# mm5833.net
KiCad netlist of a schematic drawn in EAGLE
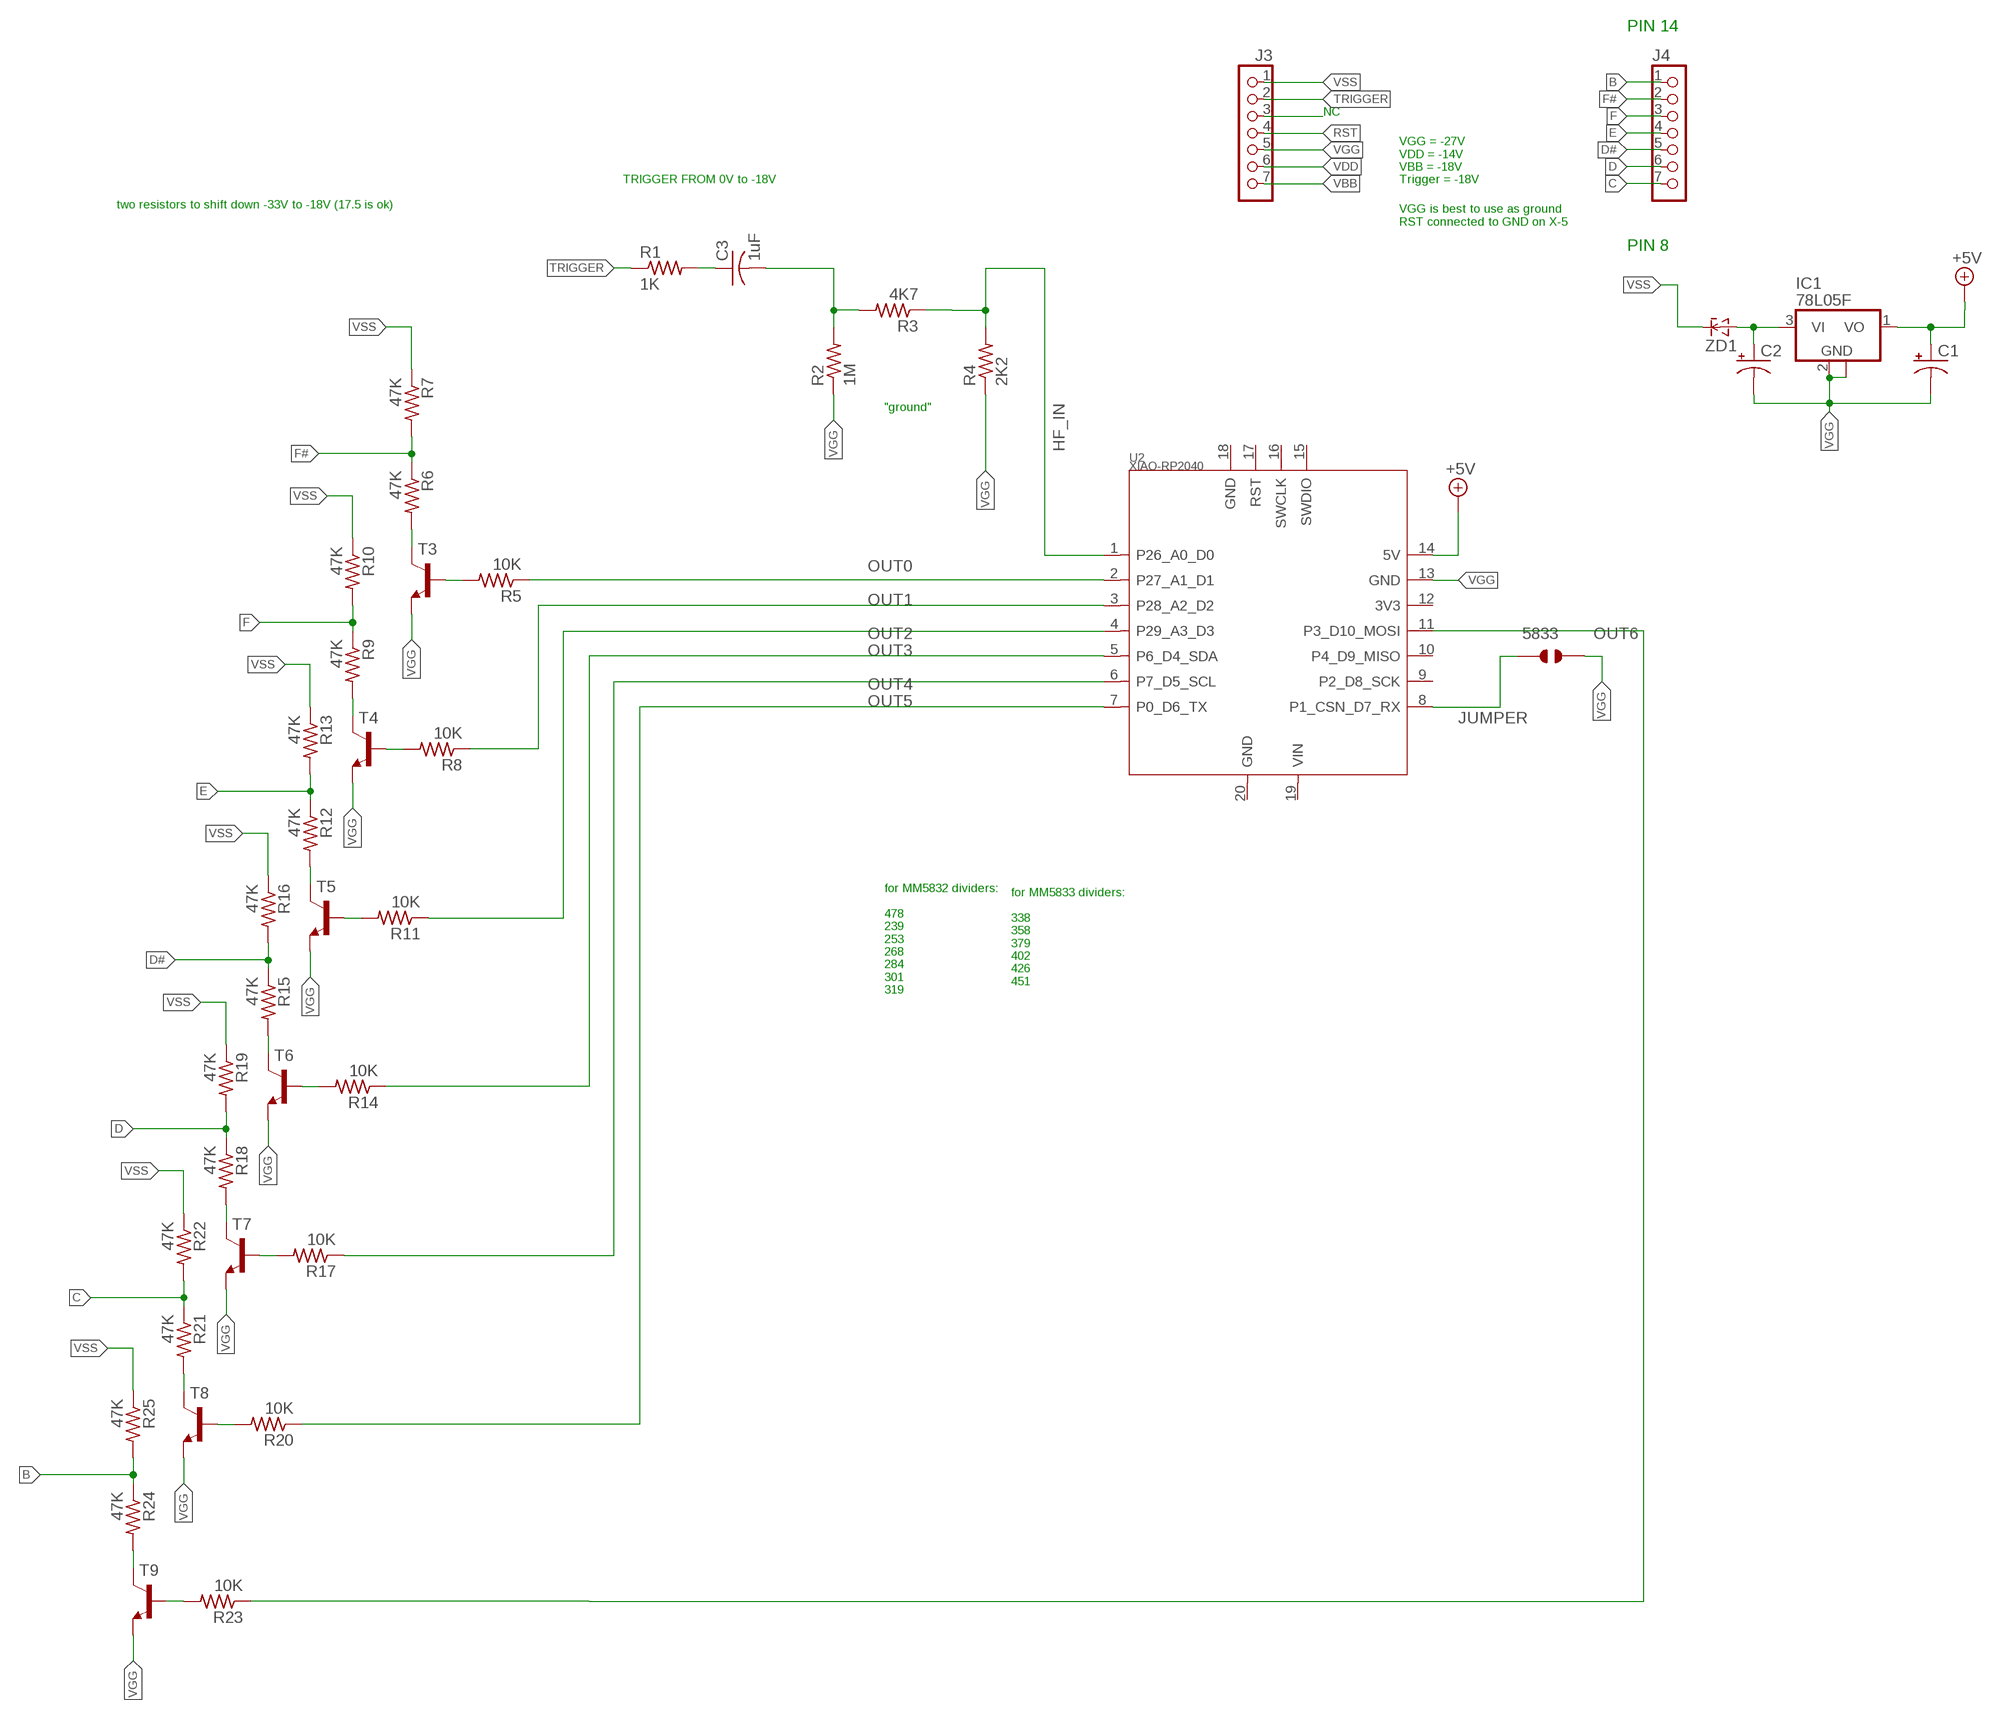
[diagram p0: schematic, sheet 1]

(export (version "E")
  (design (tool "Eeschema 10.0.6"))
  (components
    (comp (ref "5833")
      (value "JUMPER_SOLDER_1X2")
      (footprint "eagle-import:JUMPER_SOLDER_1X2")
      (libsource (lib "eagle-import") (part "JUMPER_SOLDER_1X2"))
    )
    (comp (ref "C1")
      (value "CPOL-USA/3216-18R")
      (footprint "eagle-import:A_3216-18R")
      (libsource (lib "eagle-import") (part "CPOL-USA/3216-18R"))
    )
    (comp (ref "C2")
      (value "CPOL-USA/3216-18R")
      (footprint "eagle-import:A_3216-18R")
      (libsource (lib "eagle-import") (part "CPOL-USA/3216-18R"))
    )
    (comp (ref "C3")
      (value "1uF")
      (footprint "eagle-import:C0805")
      (libsource (lib "eagle-import") (part "C-USC0805"))
    )
    (comp (ref "IC1")
      (value "78L05F")
      (footprint "eagle-import:SOT89")
      (libsource (lib "eagle-import") (part "78LF05"))
    )
    (comp (ref "J3")
      (value "CON_HEADER_1X07")
      (footprint "eagle-import:M1X7_SMD")
      (libsource (lib "eagle-import") (part "CON_HEADER_1X07"))
    )
    (comp (ref "J4")
      (value "CON_HEADER_1X07")
      (footprint "eagle-import:M1X7_SMD")
      (libsource (lib "eagle-import") (part "CON_HEADER_1X07"))
    )
    (comp (ref "R1")
      (value "1K")
      (footprint "eagle-import:R0603")
      (libsource (lib "eagle-import") (part "R-US_R0603"))
    )
    (comp (ref "R2")
      (value "1M")
      (footprint "eagle-import:R0603")
      (libsource (lib "eagle-import") (part "R-US_R0603"))
    )
    (comp (ref "R3")
      (value "4K7")
      (footprint "eagle-import:R0603")
      (libsource (lib "eagle-import") (part "R-US_R0603"))
    )
    (comp (ref "R4")
      (value "2K2")
      (footprint "eagle-import:R0603")
      (libsource (lib "eagle-import") (part "R-US_R0603"))
    )
    (comp (ref "R5")
      (value "10K")
      (footprint "eagle-import:R0603")
      (libsource (lib "eagle-import") (part "R-US_R0603"))
    )
    (comp (ref "R6")
      (value "47K")
      (footprint "eagle-import:R0603")
      (libsource (lib "eagle-import") (part "R-US_R0603"))
    )
    (comp (ref "R7")
      (value "47K")
      (footprint "eagle-import:R0603")
      (libsource (lib "eagle-import") (part "R-US_R0603"))
    )
    (comp (ref "R8")
      (value "10K")
      (footprint "eagle-import:R0603")
      (libsource (lib "eagle-import") (part "R-US_R0603"))
    )
    (comp (ref "R9")
      (value "47K")
      (footprint "eagle-import:R0603")
      (libsource (lib "eagle-import") (part "R-US_R0603"))
    )
    (comp (ref "R10")
      (value "47K")
      (footprint "eagle-import:R0603")
      (libsource (lib "eagle-import") (part "R-US_R0603"))
    )
    (comp (ref "R11")
      (value "10K")
      (footprint "eagle-import:R0603")
      (libsource (lib "eagle-import") (part "R-US_R0603"))
    )
    (comp (ref "R12")
      (value "47K")
      (footprint "eagle-import:R0603")
      (libsource (lib "eagle-import") (part "R-US_R0603"))
    )
    (comp (ref "R13")
      (value "47K")
      (footprint "eagle-import:R0603")
      (libsource (lib "eagle-import") (part "R-US_R0603"))
    )
    (comp (ref "R14")
      (value "10K")
      (footprint "eagle-import:R0603")
      (libsource (lib "eagle-import") (part "R-US_R0603"))
    )
    (comp (ref "R15")
      (value "47K")
      (footprint "eagle-import:R0603")
      (libsource (lib "eagle-import") (part "R-US_R0603"))
    )
    (comp (ref "R16")
      (value "47K")
      (footprint "eagle-import:R0603")
      (libsource (lib "eagle-import") (part "R-US_R0603"))
    )
    (comp (ref "R17")
      (value "10K")
      (footprint "eagle-import:R0603")
      (libsource (lib "eagle-import") (part "R-US_R0603"))
    )
    (comp (ref "R18")
      (value "47K")
      (footprint "eagle-import:R0603")
      (libsource (lib "eagle-import") (part "R-US_R0603"))
    )
    (comp (ref "R19")
      (value "47K")
      (footprint "eagle-import:R0603")
      (libsource (lib "eagle-import") (part "R-US_R0603"))
    )
    (comp (ref "R20")
      (value "10K")
      (footprint "eagle-import:R0603")
      (libsource (lib "eagle-import") (part "R-US_R0603"))
    )
    (comp (ref "R21")
      (value "47K")
      (footprint "eagle-import:R0603")
      (libsource (lib "eagle-import") (part "R-US_R0603"))
    )
    (comp (ref "R22")
      (value "47K")
      (footprint "eagle-import:R0603")
      (libsource (lib "eagle-import") (part "R-US_R0603"))
    )
    (comp (ref "R23")
      (value "10K")
      (footprint "eagle-import:R0603")
      (libsource (lib "eagle-import") (part "R-US_R0603"))
    )
    (comp (ref "R24")
      (value "47K")
      (footprint "eagle-import:R0603")
      (libsource (lib "eagle-import") (part "R-US_R0603"))
    )
    (comp (ref "R25")
      (value "47K")
      (footprint "eagle-import:R0603")
      (libsource (lib "eagle-import") (part "R-US_R0603"))
    )
    (comp (ref "T3")
      (value "MMBT3904LT1-NPN-SOT23-BEC")
      (footprint "eagle-import:SOT23-BEC")
      (libsource (lib "eagle-import") (part "-NPN-SOT23-BECMMBT3904LT1"))
    )
    (comp (ref "T4")
      (value "MMBT3904LT1-NPN-SOT23-BEC")
      (footprint "eagle-import:SOT23-BEC")
      (libsource (lib "eagle-import") (part "-NPN-SOT23-BECMMBT3904LT1"))
    )
    (comp (ref "T5")
      (value "MMBT3904LT1-NPN-SOT23-BEC")
      (footprint "eagle-import:SOT23-BEC")
      (libsource (lib "eagle-import") (part "-NPN-SOT23-BECMMBT3904LT1"))
    )
    (comp (ref "T6")
      (value "MMBT3904LT1-NPN-SOT23-BEC")
      (footprint "eagle-import:SOT23-BEC")
      (libsource (lib "eagle-import") (part "-NPN-SOT23-BECMMBT3904LT1"))
    )
    (comp (ref "T7")
      (value "MMBT3904LT1-NPN-SOT23-BEC")
      (footprint "eagle-import:SOT23-BEC")
      (libsource (lib "eagle-import") (part "-NPN-SOT23-BECMMBT3904LT1"))
    )
    (comp (ref "T8")
      (value "MMBT3904LT1-NPN-SOT23-BEC")
      (footprint "eagle-import:SOT23-BEC")
      (libsource (lib "eagle-import") (part "-NPN-SOT23-BECMMBT3904LT1"))
    )
    (comp (ref "T9")
      (value "MMBT3904LT1-NPN-SOT23-BEC")
      (footprint "eagle-import:SOT23-BEC")
      (libsource (lib "eagle-import") (part "-NPN-SOT23-BECMMBT3904LT1"))
    )
    (comp (ref "U2")
      (value "XIAO-RP2040")
      (footprint "eagle-import:XIAO-SAMD21_RP2040-MODULE14P-2.54-21X17.8MM")
      (libsource (lib "eagle-import") (part "XIAO-RP2040"))
    )
    (comp (ref "ZD1")
      (value "ZENERSOD-123")
      (footprint "eagle-import:SOD-123")
      (libsource (lib "eagle-import") (part "ZENERSOD-123"))
    )
  )
  (nets
    (net (code "1") (name "+5V") (class "Default")
      (node (ref "C1") (pin "+") (pinfunction "+_+") (pintype "passive"))
      (node (ref "IC1") (pin "1") (pinfunction "VO_1") (pintype "passive"))
      (node (ref "U2") (pin "14") (pinfunction "5V_14") (pintype "bidirectional"))
    )
    (net (code "2") (name "/HF_IN") (class "Default")
      (node (ref "R3") (pin "1") (pinfunction "1_1") (pintype "passive"))
      (node (ref "R4") (pin "2") (pinfunction "2_2") (pintype "passive"))
      (node (ref "U2") (pin "1") (pinfunction "P26_A0_D0_1") (pintype "bidirectional"))
    )
    (net (code "3") (name "/JUMPER") (class "Default")
      (node (ref "5833") (pin "1") (pinfunction "1_1") (pintype "passive"))
      (node (ref "U2") (pin "8") (pinfunction "P1_CSN_D7_RX_8") (pintype "bidirectional"))
    )
    (net (code "4") (name "/OUT0") (class "Default")
      (node (ref "R5") (pin "1") (pinfunction "1_1") (pintype "passive"))
      (node (ref "U2") (pin "2") (pinfunction "P27_A1_D1_2") (pintype "bidirectional"))
    )
    (net (code "5") (name "/OUT1") (class "Default")
      (node (ref "R8") (pin "1") (pinfunction "1_1") (pintype "passive"))
      (node (ref "U2") (pin "3") (pinfunction "P28_A2_D2_3") (pintype "bidirectional"))
    )
    (net (code "6") (name "/OUT2") (class "Default")
      (node (ref "R11") (pin "1") (pinfunction "1_1") (pintype "passive"))
      (node (ref "U2") (pin "4") (pinfunction "P29_A3_D3_4") (pintype "bidirectional"))
    )
    (net (code "7") (name "/OUT3") (class "Default")
      (node (ref "R14") (pin "1") (pinfunction "1_1") (pintype "passive"))
      (node (ref "U2") (pin "5") (pinfunction "P6_D4_SDA_5") (pintype "bidirectional"))
    )
    (net (code "8") (name "/OUT4") (class "Default")
      (node (ref "R17") (pin "1") (pinfunction "1_1") (pintype "passive"))
      (node (ref "U2") (pin "6") (pinfunction "P7_D5_SCL_6") (pintype "bidirectional"))
    )
    (net (code "9") (name "/OUT5") (class "Default")
      (node (ref "R20") (pin "1") (pinfunction "1_1") (pintype "passive"))
      (node (ref "U2") (pin "7") (pinfunction "P0_D6_TX_7") (pintype "bidirectional"))
    )
    (net (code "10") (name "/OUT6") (class "Default")
      (node (ref "R23") (pin "1") (pinfunction "1_1") (pintype "passive"))
      (node (ref "U2") (pin "11") (pinfunction "P3_D10_MOSI_11") (pintype "bidirectional"))
    )
    (net (code "11") (name "B") (class "Default")
      (node (ref "J4") (pin "1") (pinfunction "1_1") (pintype "passive"))
      (node (ref "R24") (pin "1") (pinfunction "1_1") (pintype "passive"))
      (node (ref "R25") (pin "2") (pinfunction "2_2") (pintype "passive"))
    )
    (net (code "12") (name "C") (class "Default")
      (node (ref "J4") (pin "7") (pinfunction "7_7") (pintype "passive"))
      (node (ref "R21") (pin "1") (pinfunction "1_1") (pintype "passive"))
      (node (ref "R22") (pin "2") (pinfunction "2_2") (pintype "passive"))
    )
    (net (code "13") (name "D") (class "Default")
      (node (ref "J4") (pin "6") (pinfunction "6_6") (pintype "passive"))
      (node (ref "R18") (pin "1") (pinfunction "1_1") (pintype "passive"))
      (node (ref "R19") (pin "2") (pinfunction "2_2") (pintype "passive"))
    )
    (net (code "14") (name "D#") (class "Default")
      (node (ref "J4") (pin "5") (pinfunction "5_5") (pintype "passive"))
      (node (ref "R15") (pin "1") (pinfunction "1_1") (pintype "passive"))
      (node (ref "R16") (pin "2") (pinfunction "2_2") (pintype "passive"))
    )
    (net (code "15") (name "E") (class "Default")
      (node (ref "J4") (pin "4") (pinfunction "4_4") (pintype "passive"))
      (node (ref "R12") (pin "1") (pinfunction "1_1") (pintype "passive"))
      (node (ref "R13") (pin "2") (pinfunction "2_2") (pintype "passive"))
    )
    (net (code "16") (name "F") (class "Default")
      (node (ref "J4") (pin "3") (pinfunction "3_3") (pintype "passive"))
      (node (ref "R10") (pin "2") (pinfunction "2_2") (pintype "passive"))
      (node (ref "R9") (pin "1") (pinfunction "1_1") (pintype "passive"))
    )
    (net (code "17") (name "F#") (class "Default")
      (node (ref "J4") (pin "2") (pinfunction "2_2") (pintype "passive"))
      (node (ref "R6") (pin "1") (pinfunction "1_1") (pintype "passive"))
      (node (ref "R7") (pin "2") (pinfunction "2_2") (pintype "passive"))
    )
    (net (code "18") (name "Net-(C3-Pad1)") (class "Default")
      (node (ref "C3") (pin "1") (pinfunction "1_1") (pintype "passive"))
      (node (ref "R1") (pin "2") (pinfunction "2_2") (pintype "passive"))
    )
    (net (code "19") (name "Net-(C3-Pad2)") (class "Default")
      (node (ref "C3") (pin "2") (pinfunction "2_2") (pintype "passive"))
      (node (ref "R2") (pin "2") (pinfunction "2_2") (pintype "passive"))
      (node (ref "R3") (pin "2") (pinfunction "2_2") (pintype "passive"))
    )
    (net (code "20") (name "Net-(IC1-VI)") (class "Default")
      (node (ref "C2") (pin "+") (pinfunction "+_+") (pintype "passive"))
      (node (ref "IC1") (pin "3") (pinfunction "VI_3") (pintype "input"))
      (node (ref "ZD1") (pin "A") (pinfunction "A_A") (pintype "passive"))
    )
    (net (code "21") (name "Net-(R5-Pad2)") (class "Default")
      (node (ref "R5") (pin "2") (pinfunction "2_2") (pintype "passive"))
      (node (ref "T3") (pin "B") (pinfunction "B_B") (pintype "passive"))
    )
    (net (code "22") (name "Net-(R6-Pad2)") (class "Default")
      (node (ref "R6") (pin "2") (pinfunction "2_2") (pintype "passive"))
      (node (ref "T3") (pin "C") (pinfunction "C_C") (pintype "passive"))
    )
    (net (code "23") (name "Net-(R8-Pad2)") (class "Default")
      (node (ref "R8") (pin "2") (pinfunction "2_2") (pintype "passive"))
      (node (ref "T4") (pin "B") (pinfunction "B_B") (pintype "passive"))
    )
    (net (code "24") (name "Net-(R9-Pad2)") (class "Default")
      (node (ref "R9") (pin "2") (pinfunction "2_2") (pintype "passive"))
      (node (ref "T4") (pin "C") (pinfunction "C_C") (pintype "passive"))
    )
    (net (code "25") (name "Net-(R11-Pad2)") (class "Default")
      (node (ref "R11") (pin "2") (pinfunction "2_2") (pintype "passive"))
      (node (ref "T5") (pin "B") (pinfunction "B_B") (pintype "passive"))
    )
    (net (code "26") (name "Net-(R12-Pad2)") (class "Default")
      (node (ref "R12") (pin "2") (pinfunction "2_2") (pintype "passive"))
      (node (ref "T5") (pin "C") (pinfunction "C_C") (pintype "passive"))
    )
    (net (code "27") (name "Net-(R14-Pad2)") (class "Default")
      (node (ref "R14") (pin "2") (pinfunction "2_2") (pintype "passive"))
      (node (ref "T6") (pin "B") (pinfunction "B_B") (pintype "passive"))
    )
    (net (code "28") (name "Net-(R15-Pad2)") (class "Default")
      (node (ref "R15") (pin "2") (pinfunction "2_2") (pintype "passive"))
      (node (ref "T6") (pin "C") (pinfunction "C_C") (pintype "passive"))
    )
    (net (code "29") (name "Net-(R17-Pad2)") (class "Default")
      (node (ref "R17") (pin "2") (pinfunction "2_2") (pintype "passive"))
      (node (ref "T7") (pin "B") (pinfunction "B_B") (pintype "passive"))
    )
    (net (code "30") (name "Net-(R18-Pad2)") (class "Default")
      (node (ref "R18") (pin "2") (pinfunction "2_2") (pintype "passive"))
      (node (ref "T7") (pin "C") (pinfunction "C_C") (pintype "passive"))
    )
    (net (code "31") (name "Net-(R20-Pad2)") (class "Default")
      (node (ref "R20") (pin "2") (pinfunction "2_2") (pintype "passive"))
      (node (ref "T8") (pin "B") (pinfunction "B_B") (pintype "passive"))
    )
    (net (code "32") (name "Net-(R21-Pad2)") (class "Default")
      (node (ref "R21") (pin "2") (pinfunction "2_2") (pintype "passive"))
      (node (ref "T8") (pin "C") (pinfunction "C_C") (pintype "passive"))
    )
    (net (code "33") (name "Net-(R23-Pad2)") (class "Default")
      (node (ref "R23") (pin "2") (pinfunction "2_2") (pintype "passive"))
      (node (ref "T9") (pin "B") (pinfunction "B_B") (pintype "passive"))
    )
    (net (code "34") (name "Net-(R24-Pad2)") (class "Default")
      (node (ref "R24") (pin "2") (pinfunction "2_2") (pintype "passive"))
      (node (ref "T9") (pin "C") (pinfunction "C_C") (pintype "passive"))
    )
    (net (code "35") (name "RST") (class "Default")
      (node (ref "J3") (pin "4") (pinfunction "4_4") (pintype "passive"))
    )
    (net (code "36") (name "TRIGGER") (class "Default")
      (node (ref "J3") (pin "2") (pinfunction "2_2") (pintype "passive"))
      (node (ref "R1") (pin "1") (pinfunction "1_1") (pintype "passive"))
    )
    (net (code "37") (name "VBB") (class "Default")
      (node (ref "J3") (pin "7") (pinfunction "7_7") (pintype "passive"))
    )
    (net (code "38") (name "VDD") (class "Default")
      (node (ref "J3") (pin "6") (pinfunction "6_6") (pintype "passive"))
    )
    (net (code "39") (name "VGG") (class "Default")
      (node (ref "5833") (pin "2") (pinfunction "2_2") (pintype "passive"))
      (node (ref "C1") (pin "-") (pinfunction "-_-") (pintype "passive"))
      (node (ref "C2") (pin "-") (pinfunction "-_-") (pintype "passive"))
      (node (ref "IC1") (pin "2") (pinfunction "GND_2") (pintype "passive"))
      (node (ref "IC1") (pin "2@1") (pinfunction "GND_2@1") (pintype "passive"))
      (node (ref "J3") (pin "5") (pinfunction "5_5") (pintype "passive"))
      (node (ref "R2") (pin "1") (pinfunction "1_1") (pintype "passive"))
      (node (ref "R4") (pin "1") (pinfunction "1_1") (pintype "passive"))
      (node (ref "T3") (pin "E") (pinfunction "E_E") (pintype "passive"))
      (node (ref "T4") (pin "E") (pinfunction "E_E") (pintype "passive"))
      (node (ref "T5") (pin "E") (pinfunction "E_E") (pintype "passive"))
      (node (ref "T6") (pin "E") (pinfunction "E_E") (pintype "passive"))
      (node (ref "T7") (pin "E") (pinfunction "E_E") (pintype "passive"))
      (node (ref "T8") (pin "E") (pinfunction "E_E") (pintype "passive"))
      (node (ref "T9") (pin "E") (pinfunction "E_E") (pintype "passive"))
      (node (ref "U2") (pin "13") (pinfunction "GND_13") (pintype "bidirectional"))
    )
    (net (code "40") (name "VSS") (class "Default")
      (node (ref "J3") (pin "1") (pinfunction "1_1") (pintype "passive"))
      (node (ref "R10") (pin "1") (pinfunction "1_1") (pintype "passive"))
      (node (ref "R13") (pin "1") (pinfunction "1_1") (pintype "passive"))
      (node (ref "R16") (pin "1") (pinfunction "1_1") (pintype "passive"))
      (node (ref "R19") (pin "1") (pinfunction "1_1") (pintype "passive"))
      (node (ref "R22") (pin "1") (pinfunction "1_1") (pintype "passive"))
      (node (ref "R25") (pin "1") (pinfunction "1_1") (pintype "passive"))
      (node (ref "R7") (pin "1") (pinfunction "1_1") (pintype "passive"))
      (node (ref "ZD1") (pin "C") (pinfunction "C_C") (pintype "passive"))
    )
    (net (code "41") (name "unconnected-(J3-Pad3)") (class "Default")
      (node (ref "J3") (pin "3") (pinfunction "3_3") (pintype "passive"))
    )
    (net (code "42") (name "unconnected-(U2-3V3-Pad12)") (class "Default")
      (node (ref "U2") (pin "12") (pinfunction "3V3_12") (pintype "bidirectional"))
    )
    (net (code "43") (name "unconnected-(U2-GND-Pad18)") (class "Default")
      (node (ref "U2") (pin "18") (pinfunction "GND_18") (pintype "bidirectional"))
    )
    (net (code "44") (name "unconnected-(U2-GND-Pad20)") (class "Default")
      (node (ref "U2") (pin "20") (pinfunction "GND_20") (pintype "bidirectional"))
    )
    (net (code "45") (name "unconnected-(U2-P2_D8_SCK-Pad9)") (class "Default")
      (node (ref "U2") (pin "9") (pinfunction "P2_D8_SCK_9") (pintype "bidirectional"))
    )
    (net (code "46") (name "unconnected-(U2-P4_D9_MISO-Pad10)") (class "Default")
      (node (ref "U2") (pin "10") (pinfunction "P4_D9_MISO_10") (pintype "bidirectional"))
    )
    (net (code "47") (name "unconnected-(U2-RST-Pad17)") (class "Default")
      (node (ref "U2") (pin "17") (pinfunction "RST_17") (pintype "bidirectional"))
    )
    (net (code "48") (name "unconnected-(U2-SWCLK-Pad16)") (class "Default")
      (node (ref "U2") (pin "16") (pinfunction "SWCLK_16") (pintype "bidirectional"))
    )
    (net (code "49") (name "unconnected-(U2-SWDIO-Pad15)") (class "Default")
      (node (ref "U2") (pin "15") (pinfunction "SWDIO_15") (pintype "bidirectional"))
    )
    (net (code "50") (name "unconnected-(U2-VIN-Pad19)") (class "Default")
      (node (ref "U2") (pin "19") (pinfunction "VIN_19") (pintype "bidirectional"))
    )
  )
)
